# 01-CM4_Conn.net
KiCad netlist of a schematic drawn in Altium Designer
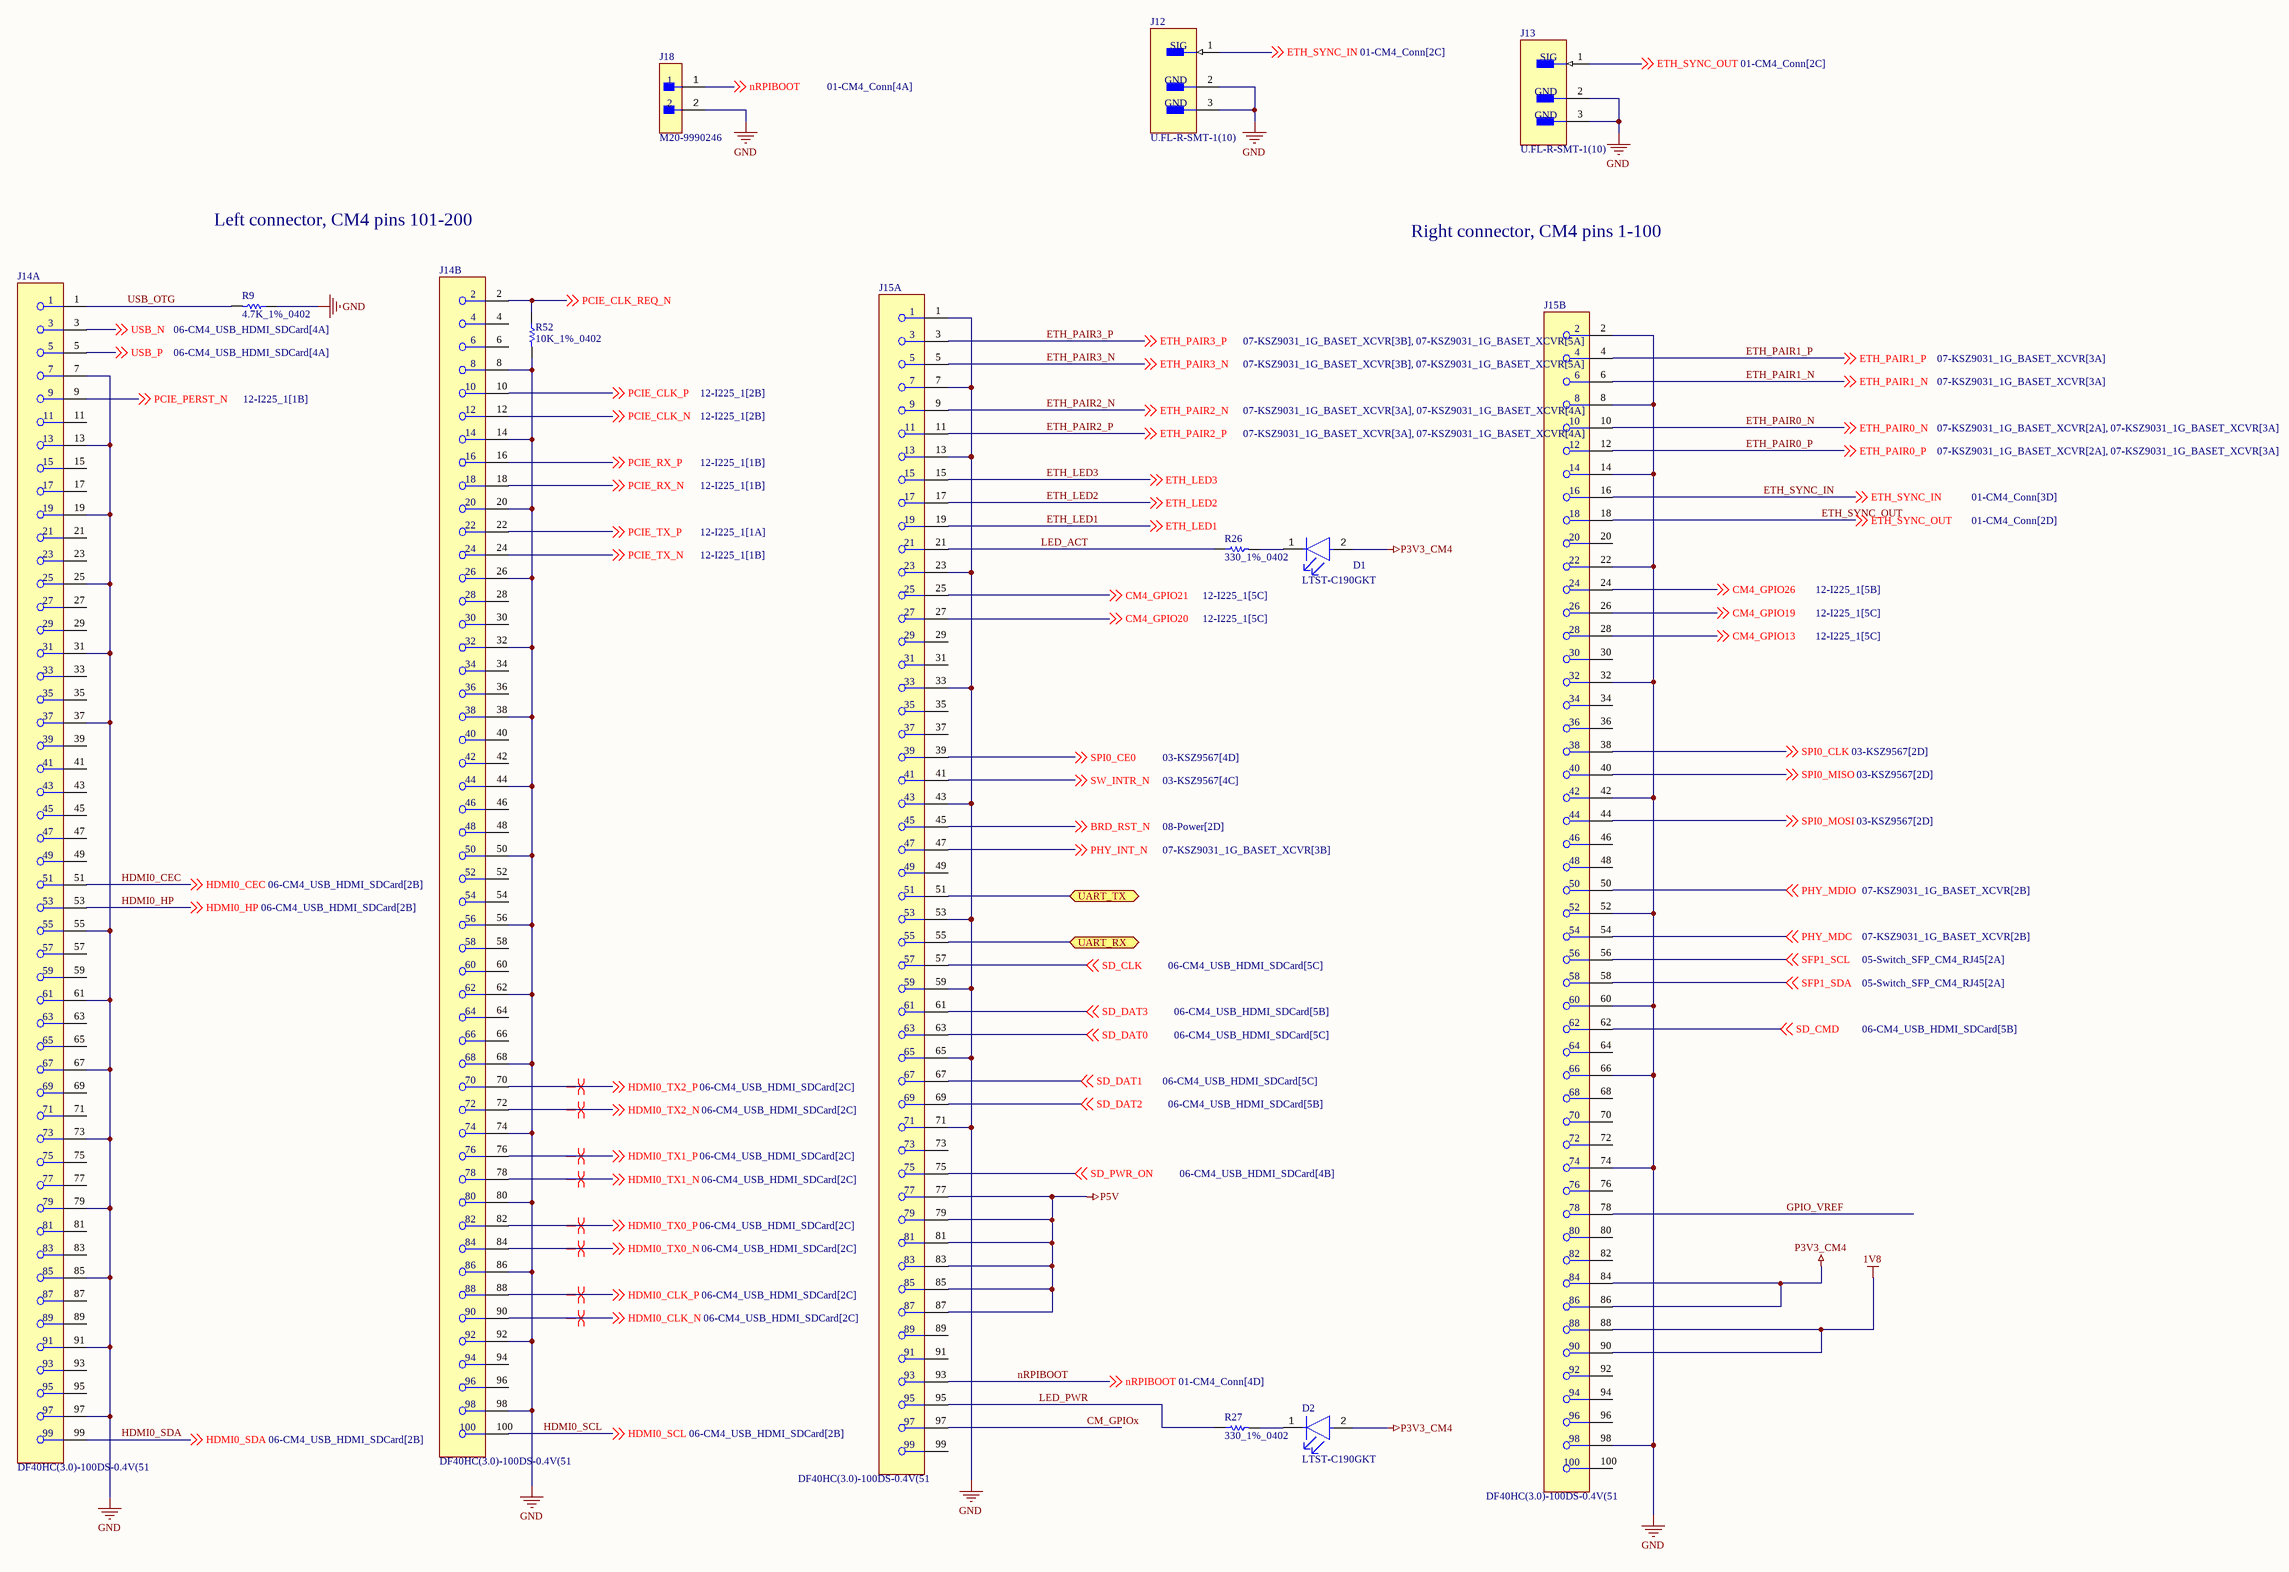
[diagram p0: 01-CM4_Conn.SchDoc]

(export (version "E")
  (design (tool "Eeschema 10.0.6"))
  (components
    (comp (ref "D1")
      (value "LTST-C190GKT")
      (footprint "FP-LTST-C190GKT-MFG")
      (description "LED GREEN CLEAR CHIP SMD")
      (fields (field (name "VOLTAGE") "2V"))
      (libsource (lib "Altium Content Vault") (part "8706943c75ba83719d021d2fdc84c58"))
    )
    (comp (ref "D2")
      (value "LTST-C190GKT")
      (footprint "FP-LTST-C190GKT-MFG")
      (description "LED GREEN CLEAR CHIP SMD")
      (fields (field (name "VOLTAGE") "2V"))
      (libsource (lib "Altium Content Vault") (part "8706943c75ba83719d021d2fdc84c58"))
    )
    (comp (ref "J12")
      (value "U.FL-R-SMT-1(10)")
      (footprint "FP-U_FL-R-SMT-1_10-MFG")
      (description "CONN U.FL RCPT STR 50 OHM SMD")
      (libsource (lib "Altium Content Vault") (part "7158abf7d987fa84906f6fb0d115710"))
    )
    (comp (ref "J13")
      (value "U.FL-R-SMT-1(10)")
      (footprint "FP-U_FL-R-SMT-1_10-MFG")
      (description "CONN U.FL RCPT STR 50 OHM SMD")
      (libsource (lib "Altium Content Vault") (part "7158abf7d987fa84906f6fb0d115710"))
    )
    (comp (ref "J14")
      (value "DF40HC(3.0)-100DS-0.4V(51")
      (footprint "FP-DF40HC_3_0_-100DS-0_4V-MFG")
      (description "CONN RCPT 100POS SMD GOLD")
      (libsource (lib "Altium Content Vault") (part "fa457dfecf3ebaea1b28843c89f182e"))
    )
    (comp (ref "J15")
      (value "DF40HC(3.0)-100DS-0.4V(51")
      (footprint "FP-DF40HC_3_0_-100DS-0_4V-MFG")
      (description "CONN RCPT 100POS SMD GOLD")
      (libsource (lib "Altium Content Vault") (part "fa457dfecf3ebaea1b28843c89f182e"))
    )
    (comp (ref "J18")
      (value "M20-9990246")
      (footprint "FP-M20-9990246-MFG")
      (description "CONN HEADER VERT 2POS 2.54MM")
      (fields
        (field (name "OCTOPART") "https://octopart.com/m20-9990246-harwin-2590635")
        (field (name "MANUFACTURER") "Harwin")
      )
      (libsource (lib "Altium Content Vault") (part "3bc925449376181038e59eaffc5286c"))
    )
    (comp (ref "R9")
      (value "4.7K_1%_0402")
      (footprint "RESC1005X40X25NL10T10")
      (fields (field (name "MANUFACTURER") "Bourns") (field (name "PART NUMBER") "CR0402-FX-4701GLF"))
      (libsource (lib "Altium Content Vault") (part "RES"))
    )
    (comp (ref "R26")
      (value "330_1%_0402")
      (footprint "RESC1005X40X25NL10T10")
      (fields (field (name "MANUFACTURER") "Panasonic") (field (name "PART NUMBER") "ERA-2AED331X"))
      (libsource (lib "Altium Content Vault") (part "RES"))
    )
    (comp (ref "R27")
      (value "330_1%_0402")
      (footprint "RESC1005X40X25NL10T10")
      (fields (field (name "MANUFACTURER") "Panasonic") (field (name "PART NUMBER") "ERA-2AED331X"))
      (libsource (lib "Altium Content Vault") (part "RES"))
    )
    (comp (ref "R52")
      (value "10K_1%_0402")
      (footprint "RESC1005X40X25NL10T10")
      (fields (field (name "MANUFACTURER") "Bourns") (field (name "PART NUMBER") "CR0402-FX-1002GLF"))
      (libsource (lib "Altium Content Vault") (part "RES"))
    )
  )
  (nets
    (net (code "1") (name "/CM_GPIOx") (class "Default")
      (node (ref "J15") (pin "97") (pinfunction "97_97") (pintype "passive"))
    )
    (net (code "2") (name "/GPIO_VREF") (class "Default")
      (node (ref "J15") (pin "78") (pinfunction "78_78") (pintype "passive"))
    )
    (net (code "3") (name "/LED_ACT") (class "Default")
      (node (ref "J15") (pin "21") (pinfunction "21_21") (pintype "passive"))
      (node (ref "R26") (pin "1") (pinfunction "1_1") (pintype "passive"))
    )
    (net (code "4") (name "/LED_PWR") (class "Default")
      (node (ref "J15") (pin "95") (pinfunction "95_95") (pintype "passive"))
      (node (ref "R27") (pin "1") (pinfunction "1_1") (pintype "passive"))
    )
    (net (code "5") (name "/UART_RX") (class "Default")
      (node (ref "J15") (pin "55") (pinfunction "55_55") (pintype "passive"))
    )
    (net (code "6") (name "/UART_TX") (class "Default")
      (node (ref "J15") (pin "51") (pinfunction "51_51") (pintype "passive"))
    )
    (net (code "7") (name "/USB_OTG") (class "Default")
      (node (ref "J14") (pin "1") (pinfunction "1_1") (pintype "passive"))
      (node (ref "R9") (pin "2") (pinfunction "2_2") (pintype "passive"))
    )
    (net (code "8") (name "1V8") (class "Default")
      (node (ref "J15") (pin "88") (pinfunction "88_88") (pintype "passive"))
      (node (ref "J15") (pin "90") (pinfunction "90_90") (pintype "passive"))
    )
    (net (code "9") (name "BRD_RST_N") (class "Default")
      (node (ref "J15") (pin "45") (pinfunction "45_45") (pintype "passive"))
    )
    (net (code "10") (name "CM4_GPIO13") (class "Default")
      (node (ref "J15") (pin "28") (pinfunction "28_28") (pintype "passive"))
    )
    (net (code "11") (name "CM4_GPIO19") (class "Default")
      (node (ref "J15") (pin "26") (pinfunction "26_26") (pintype "passive"))
    )
    (net (code "12") (name "CM4_GPIO20") (class "Default")
      (node (ref "J15") (pin "27") (pinfunction "27_27") (pintype "passive"))
    )
    (net (code "13") (name "CM4_GPIO21") (class "Default")
      (node (ref "J15") (pin "25") (pinfunction "25_25") (pintype "passive"))
    )
    (net (code "14") (name "CM4_GPIO26") (class "Default")
      (node (ref "J15") (pin "24") (pinfunction "24_24") (pintype "passive"))
    )
    (net (code "15") (name "ETH_LED1") (class "Default")
      (node (ref "J15") (pin "19") (pinfunction "19_19") (pintype "passive"))
    )
    (net (code "16") (name "ETH_LED2") (class "Default")
      (node (ref "J15") (pin "17") (pinfunction "17_17") (pintype "passive"))
    )
    (net (code "17") (name "ETH_LED3") (class "Default")
      (node (ref "J15") (pin "15") (pinfunction "15_15") (pintype "passive"))
    )
    (net (code "18") (name "ETH_PAIR0_N") (class "Default")
      (node (ref "J15") (pin "10") (pinfunction "10_10") (pintype "passive"))
    )
    (net (code "19") (name "ETH_PAIR0_P") (class "Default")
      (node (ref "J15") (pin "12") (pinfunction "12_12") (pintype "passive"))
    )
    (net (code "20") (name "ETH_PAIR1_N") (class "Default")
      (node (ref "J15") (pin "6") (pinfunction "6_6") (pintype "passive"))
    )
    (net (code "21") (name "ETH_PAIR1_P") (class "Default")
      (node (ref "J15") (pin "4") (pinfunction "4_4") (pintype "passive"))
    )
    (net (code "22") (name "ETH_PAIR2_N") (class "Default")
      (node (ref "J15") (pin "9") (pinfunction "9_9") (pintype "passive"))
    )
    (net (code "23") (name "ETH_PAIR2_P") (class "Default")
      (node (ref "J15") (pin "11") (pinfunction "11_11") (pintype "passive"))
    )
    (net (code "24") (name "ETH_PAIR3_N") (class "Default")
      (node (ref "J15") (pin "5") (pinfunction "5_5") (pintype "passive"))
    )
    (net (code "25") (name "ETH_PAIR3_P") (class "Default")
      (node (ref "J15") (pin "3") (pinfunction "3_3") (pintype "passive"))
    )
    (net (code "26") (name "ETH_SYNC_IN") (class "Default")
      (node (ref "J12") (pin "1") (pinfunction "SIG_1") (pintype "input"))
      (node (ref "J15") (pin "16") (pinfunction "16_16") (pintype "passive"))
    )
    (net (code "27") (name "ETH_SYNC_OUT") (class "Default")
      (node (ref "J13") (pin "1") (pinfunction "SIG_1") (pintype "input"))
      (node (ref "J15") (pin "18") (pinfunction "18_18") (pintype "passive"))
    )
    (net (code "28") (name "GND") (class "Default")
      (node (ref "J12") (pin "2") (pinfunction "GND_2") (pintype "power_in"))
      (node (ref "J12") (pin "3") (pinfunction "GND_3") (pintype "power_in"))
      (node (ref "J13") (pin "2") (pinfunction "GND_2") (pintype "power_in"))
      (node (ref "J13") (pin "3") (pinfunction "GND_3") (pintype "power_in"))
      (node (ref "J14") (pin "13") (pinfunction "13_13") (pintype "passive"))
      (node (ref "J14") (pin "14") (pinfunction "14_14") (pintype "passive"))
      (node (ref "J14") (pin "19") (pinfunction "19_19") (pintype "passive"))
      (node (ref "J14") (pin "20") (pinfunction "20_20") (pintype "passive"))
      (node (ref "J14") (pin "25") (pinfunction "25_25") (pintype "passive"))
      (node (ref "J14") (pin "26") (pinfunction "26_26") (pintype "passive"))
      (node (ref "J14") (pin "31") (pinfunction "31_31") (pintype "passive"))
      (node (ref "J14") (pin "32") (pinfunction "32_32") (pintype "passive"))
      (node (ref "J14") (pin "37") (pinfunction "37_37") (pintype "passive"))
      (node (ref "J14") (pin "38") (pinfunction "38_38") (pintype "passive"))
      (node (ref "J14") (pin "44") (pinfunction "44_44") (pintype "passive"))
      (node (ref "J14") (pin "50") (pinfunction "50_50") (pintype "passive"))
      (node (ref "J14") (pin "55") (pinfunction "55_55") (pintype "passive"))
      (node (ref "J14") (pin "56") (pinfunction "56_56") (pintype "passive"))
      (node (ref "J14") (pin "61") (pinfunction "61_61") (pintype "passive"))
      (node (ref "J14") (pin "62") (pinfunction "62_62") (pintype "passive"))
      (node (ref "J14") (pin "67") (pinfunction "67_67") (pintype "passive"))
      (node (ref "J14") (pin "68") (pinfunction "68_68") (pintype "passive"))
      (node (ref "J14") (pin "7") (pinfunction "7_7") (pintype "passive"))
      (node (ref "J14") (pin "73") (pinfunction "73_73") (pintype "passive"))
      (node (ref "J14") (pin "74") (pinfunction "74_74") (pintype "passive"))
      (node (ref "J14") (pin "79") (pinfunction "79_79") (pintype "passive"))
      (node (ref "J14") (pin "8") (pinfunction "8_8") (pintype "passive"))
      (node (ref "J14") (pin "80") (pinfunction "80_80") (pintype "passive"))
      (node (ref "J14") (pin "85") (pinfunction "85_85") (pintype "passive"))
      (node (ref "J14") (pin "86") (pinfunction "86_86") (pintype "passive"))
      (node (ref "J14") (pin "91") (pinfunction "91_91") (pintype "passive"))
      (node (ref "J14") (pin "92") (pinfunction "92_92") (pintype "passive"))
      (node (ref "J14") (pin "97") (pinfunction "97_97") (pintype "passive"))
      (node (ref "J14") (pin "98") (pinfunction "98_98") (pintype "passive"))
      (node (ref "J15") (pin "1") (pinfunction "1_1") (pintype "passive"))
      (node (ref "J15") (pin "13") (pinfunction "13_13") (pintype "passive"))
      (node (ref "J15") (pin "14") (pinfunction "14_14") (pintype "passive"))
      (node (ref "J15") (pin "2") (pinfunction "2_2") (pintype "passive"))
      (node (ref "J15") (pin "22") (pinfunction "22_22") (pintype "passive"))
      (node (ref "J15") (pin "23") (pinfunction "23_23") (pintype "passive"))
      (node (ref "J15") (pin "32") (pinfunction "32_32") (pintype "passive"))
      (node (ref "J15") (pin "33") (pinfunction "33_33") (pintype "passive"))
      (node (ref "J15") (pin "42") (pinfunction "42_42") (pintype "passive"))
      (node (ref "J15") (pin "43") (pinfunction "43_43") (pintype "passive"))
      (node (ref "J15") (pin "52") (pinfunction "52_52") (pintype "passive"))
      (node (ref "J15") (pin "53") (pinfunction "53_53") (pintype "passive"))
      (node (ref "J15") (pin "59") (pinfunction "59_59") (pintype "passive"))
      (node (ref "J15") (pin "60") (pinfunction "60_60") (pintype "passive"))
      (node (ref "J15") (pin "65") (pinfunction "65_65") (pintype "passive"))
      (node (ref "J15") (pin "66") (pinfunction "66_66") (pintype "passive"))
      (node (ref "J15") (pin "7") (pinfunction "7_7") (pintype "passive"))
      (node (ref "J15") (pin "71") (pinfunction "71_71") (pintype "passive"))
      (node (ref "J15") (pin "74") (pinfunction "74_74") (pintype "passive"))
      (node (ref "J15") (pin "8") (pinfunction "8_8") (pintype "passive"))
      (node (ref "J15") (pin "98") (pinfunction "98_98") (pintype "passive"))
      (node (ref "J18") (pin "2") (pinfunction "2_2") (pintype "passive"))
      (node (ref "R52") (pin "2") (pinfunction "2_2") (pintype "passive"))
      (node (ref "R9") (pin "1") (pinfunction "1_1") (pintype "passive"))
    )
    (net (code "29") (name "HDMI0_CEC") (class "Default")
      (node (ref "J14") (pin "51") (pinfunction "51_51") (pintype "passive"))
    )
    (net (code "30") (name "HDMI0_CLK_N") (class "Default")
      (node (ref "J14") (pin "90") (pinfunction "90_90") (pintype "passive"))
    )
    (net (code "31") (name "HDMI0_CLK_P") (class "Default")
      (node (ref "J14") (pin "88") (pinfunction "88_88") (pintype "passive"))
    )
    (net (code "32") (name "HDMI0_HP") (class "Default")
      (node (ref "J14") (pin "53") (pinfunction "53_53") (pintype "passive"))
    )
    (net (code "33") (name "HDMI0_SCL") (class "Default")
      (node (ref "J14") (pin "100") (pinfunction "100_100") (pintype "passive"))
    )
    (net (code "34") (name "HDMI0_SDA") (class "Default")
      (node (ref "J14") (pin "99") (pinfunction "99_99") (pintype "passive"))
    )
    (net (code "35") (name "HDMI0_TX0_N") (class "Default")
      (node (ref "J14") (pin "84") (pinfunction "84_84") (pintype "passive"))
    )
    (net (code "36") (name "HDMI0_TX0_P") (class "Default")
      (node (ref "J14") (pin "82") (pinfunction "82_82") (pintype "passive"))
    )
    (net (code "37") (name "HDMI0_TX1_N") (class "Default")
      (node (ref "J14") (pin "78") (pinfunction "78_78") (pintype "passive"))
    )
    (net (code "38") (name "HDMI0_TX1_P") (class "Default")
      (node (ref "J14") (pin "76") (pinfunction "76_76") (pintype "passive"))
    )
    (net (code "39") (name "HDMI0_TX2_N") (class "Default")
      (node (ref "J14") (pin "72") (pinfunction "72_72") (pintype "passive"))
    )
    (net (code "40") (name "HDMI0_TX2_P") (class "Default")
      (node (ref "J14") (pin "70") (pinfunction "70_70") (pintype "passive"))
    )
    (net (code "41") (name "Net-(D1-C)") (class "Default")
      (node (ref "D1") (pin "1") (pinfunction "C_1") (pintype "passive"))
      (node (ref "R26") (pin "2") (pinfunction "2_2") (pintype "passive"))
    )
    (net (code "42") (name "Net-(D2-C)") (class "Default")
      (node (ref "D2") (pin "1") (pinfunction "C_1") (pintype "passive"))
      (node (ref "R27") (pin "2") (pinfunction "2_2") (pintype "passive"))
    )
    (net (code "43") (name "P3V3_CM4") (class "Default")
      (node (ref "D1") (pin "2") (pinfunction "A_2") (pintype "passive"))
      (node (ref "D2") (pin "2") (pinfunction "A_2") (pintype "passive"))
      (node (ref "J15") (pin "84") (pinfunction "84_84") (pintype "passive"))
      (node (ref "J15") (pin "86") (pinfunction "86_86") (pintype "passive"))
    )
    (net (code "44") (name "P5V") (class "Default")
      (node (ref "J15") (pin "77") (pinfunction "77_77") (pintype "passive"))
      (node (ref "J15") (pin "79") (pinfunction "79_79") (pintype "passive"))
      (node (ref "J15") (pin "81") (pinfunction "81_81") (pintype "passive"))
      (node (ref "J15") (pin "83") (pinfunction "83_83") (pintype "passive"))
      (node (ref "J15") (pin "85") (pinfunction "85_85") (pintype "passive"))
      (node (ref "J15") (pin "87") (pinfunction "87_87") (pintype "passive"))
    )
    (net (code "45") (name "PCIE_CLK_N") (class "Default")
      (node (ref "J14") (pin "12") (pinfunction "12_12") (pintype "passive"))
    )
    (net (code "46") (name "PCIE_CLK_P") (class "Default")
      (node (ref "J14") (pin "10") (pinfunction "10_10") (pintype "passive"))
    )
    (net (code "47") (name "PCIE_CLK_REQ_N") (class "Default")
      (node (ref "J14") (pin "2") (pinfunction "2_2") (pintype "passive"))
      (node (ref "R52") (pin "1") (pinfunction "1_1") (pintype "passive"))
    )
    (net (code "48") (name "PCIE_PERST_N") (class "Default")
      (node (ref "J14") (pin "9") (pinfunction "9_9") (pintype "passive"))
    )
    (net (code "49") (name "PCIE_RX_N") (class "Default")
      (node (ref "J14") (pin "18") (pinfunction "18_18") (pintype "passive"))
    )
    (net (code "50") (name "PCIE_RX_P") (class "Default")
      (node (ref "J14") (pin "16") (pinfunction "16_16") (pintype "passive"))
    )
    (net (code "51") (name "PCIE_TX_N") (class "Default")
      (node (ref "J14") (pin "24") (pinfunction "24_24") (pintype "passive"))
    )
    (net (code "52") (name "PCIE_TX_P") (class "Default")
      (node (ref "J14") (pin "22") (pinfunction "22_22") (pintype "passive"))
    )
    (net (code "53") (name "PHY_INT_N") (class "Default")
      (node (ref "J15") (pin "47") (pinfunction "47_47") (pintype "passive"))
    )
    (net (code "54") (name "PHY_MDC") (class "Default")
      (node (ref "J15") (pin "54") (pinfunction "54_54") (pintype "passive"))
    )
    (net (code "55") (name "PHY_MDIO") (class "Default")
      (node (ref "J15") (pin "50") (pinfunction "50_50") (pintype "passive"))
    )
    (net (code "56") (name "SD_CLK") (class "Default")
      (node (ref "J15") (pin "57") (pinfunction "57_57") (pintype "passive"))
    )
    (net (code "57") (name "SD_CMD") (class "Default")
      (node (ref "J15") (pin "62") (pinfunction "62_62") (pintype "passive"))
    )
    (net (code "58") (name "SD_DAT0") (class "Default")
      (node (ref "J15") (pin "63") (pinfunction "63_63") (pintype "passive"))
    )
    (net (code "59") (name "SD_DAT1") (class "Default")
      (node (ref "J15") (pin "67") (pinfunction "67_67") (pintype "passive"))
    )
    (net (code "60") (name "SD_DAT2") (class "Default")
      (node (ref "J15") (pin "69") (pinfunction "69_69") (pintype "passive"))
    )
    (net (code "61") (name "SD_DAT3") (class "Default")
      (node (ref "J15") (pin "61") (pinfunction "61_61") (pintype "passive"))
    )
    (net (code "62") (name "SD_PWR_ON") (class "Default")
      (node (ref "J15") (pin "75") (pinfunction "75_75") (pintype "passive"))
    )
    (net (code "63") (name "SFP1_SCL") (class "Default")
      (node (ref "J15") (pin "56") (pinfunction "56_56") (pintype "passive"))
    )
    (net (code "64") (name "SFP1_SDA") (class "Default")
      (node (ref "J15") (pin "58") (pinfunction "58_58") (pintype "passive"))
    )
    (net (code "65") (name "SPI0_CE0") (class "Default")
      (node (ref "J15") (pin "39") (pinfunction "39_39") (pintype "passive"))
    )
    (net (code "66") (name "SPI0_CLK") (class "Default")
      (node (ref "J15") (pin "38") (pinfunction "38_38") (pintype "passive"))
    )
    (net (code "67") (name "SPI0_MISO") (class "Default")
      (node (ref "J15") (pin "40") (pinfunction "40_40") (pintype "passive"))
    )
    (net (code "68") (name "SPI0_MOSI") (class "Default")
      (node (ref "J15") (pin "44") (pinfunction "44_44") (pintype "passive"))
    )
    (net (code "69") (name "SW_INTR_N") (class "Default")
      (node (ref "J15") (pin "41") (pinfunction "41_41") (pintype "passive"))
    )
    (net (code "70") (name "USB_N") (class "Default")
      (node (ref "J14") (pin "3") (pinfunction "3_3") (pintype "passive"))
    )
    (net (code "71") (name "USB_P") (class "Default")
      (node (ref "J14") (pin "5") (pinfunction "5_5") (pintype "passive"))
    )
    (net (code "72") (name "nRPIBOOT") (class "Default")
      (node (ref "J15") (pin "93") (pinfunction "93_93") (pintype "passive"))
      (node (ref "J18") (pin "1") (pinfunction "1_1") (pintype "passive"))
    )
    (net (code "73") (name "unconnected-(J14-Pad4)") (class "Default")
      (node (ref "J14") (pin "4") (pinfunction "4_4") (pintype "passive"))
    )
    (net (code "74") (name "unconnected-(J14-Pad6)") (class "Default")
      (node (ref "J14") (pin "6") (pinfunction "6_6") (pintype "passive"))
    )
    (net (code "75") (name "unconnected-(J14-Pad11)") (class "Default")
      (node (ref "J14") (pin "11") (pinfunction "11_11") (pintype "passive"))
    )
    (net (code "76") (name "unconnected-(J14-Pad15)") (class "Default")
      (node (ref "J14") (pin "15") (pinfunction "15_15") (pintype "passive"))
    )
    (net (code "77") (name "unconnected-(J14-Pad17)") (class "Default")
      (node (ref "J14") (pin "17") (pinfunction "17_17") (pintype "passive"))
    )
    (net (code "78") (name "unconnected-(J14-Pad21)") (class "Default")
      (node (ref "J14") (pin "21") (pinfunction "21_21") (pintype "passive"))
    )
    (net (code "79") (name "unconnected-(J14-Pad23)") (class "Default")
      (node (ref "J14") (pin "23") (pinfunction "23_23") (pintype "passive"))
    )
    (net (code "80") (name "unconnected-(J14-Pad27)") (class "Default")
      (node (ref "J14") (pin "27") (pinfunction "27_27") (pintype "passive"))
    )
    (net (code "81") (name "unconnected-(J14-Pad28)") (class "Default")
      (node (ref "J14") (pin "28") (pinfunction "28_28") (pintype "passive"))
    )
    (net (code "82") (name "unconnected-(J14-Pad29)") (class "Default")
      (node (ref "J14") (pin "29") (pinfunction "29_29") (pintype "passive"))
    )
    (net (code "83") (name "unconnected-(J14-Pad30)") (class "Default")
      (node (ref "J14") (pin "30") (pinfunction "30_30") (pintype "passive"))
    )
    (net (code "84") (name "unconnected-(J14-Pad33)") (class "Default")
      (node (ref "J14") (pin "33") (pinfunction "33_33") (pintype "passive"))
    )
    (net (code "85") (name "unconnected-(J14-Pad34)") (class "Default")
      (node (ref "J14") (pin "34") (pinfunction "34_34") (pintype "passive"))
    )
    (net (code "86") (name "unconnected-(J14-Pad35)") (class "Default")
      (node (ref "J14") (pin "35") (pinfunction "35_35") (pintype "passive"))
    )
    (net (code "87") (name "unconnected-(J14-Pad36)") (class "Default")
      (node (ref "J14") (pin "36") (pinfunction "36_36") (pintype "passive"))
    )
    (net (code "88") (name "unconnected-(J14-Pad39)") (class "Default")
      (node (ref "J14") (pin "39") (pinfunction "39_39") (pintype "passive"))
    )
    (net (code "89") (name "unconnected-(J14-Pad40)") (class "Default")
      (node (ref "J14") (pin "40") (pinfunction "40_40") (pintype "passive"))
    )
    (net (code "90") (name "unconnected-(J14-Pad41)") (class "Default")
      (node (ref "J14") (pin "41") (pinfunction "41_41") (pintype "passive"))
    )
    (net (code "91") (name "unconnected-(J14-Pad42)") (class "Default")
      (node (ref "J14") (pin "42") (pinfunction "42_42") (pintype "passive"))
    )
    (net (code "92") (name "unconnected-(J14-Pad43)") (class "Default")
      (node (ref "J14") (pin "43") (pinfunction "43_43") (pintype "passive"))
    )
    (net (code "93") (name "unconnected-(J14-Pad45)") (class "Default")
      (node (ref "J14") (pin "45") (pinfunction "45_45") (pintype "passive"))
    )
    (net (code "94") (name "unconnected-(J14-Pad46)") (class "Default")
      (node (ref "J14") (pin "46") (pinfunction "46_46") (pintype "passive"))
    )
    (net (code "95") (name "unconnected-(J14-Pad47)") (class "Default")
      (node (ref "J14") (pin "47") (pinfunction "47_47") (pintype "passive"))
    )
    (net (code "96") (name "unconnected-(J14-Pad48)") (class "Default")
      (node (ref "J14") (pin "48") (pinfunction "48_48") (pintype "passive"))
    )
    (net (code "97") (name "unconnected-(J14-Pad49)") (class "Default")
      (node (ref "J14") (pin "49") (pinfunction "49_49") (pintype "passive"))
    )
    (net (code "98") (name "unconnected-(J14-Pad52)") (class "Default")
      (node (ref "J14") (pin "52") (pinfunction "52_52") (pintype "passive"))
    )
    (net (code "99") (name "unconnected-(J14-Pad54)") (class "Default")
      (node (ref "J14") (pin "54") (pinfunction "54_54") (pintype "passive"))
    )
    (net (code "100") (name "unconnected-(J14-Pad57)") (class "Default")
      (node (ref "J14") (pin "57") (pinfunction "57_57") (pintype "passive"))
    )
    (net (code "101") (name "unconnected-(J14-Pad58)") (class "Default")
      (node (ref "J14") (pin "58") (pinfunction "58_58") (pintype "passive"))
    )
    (net (code "102") (name "unconnected-(J14-Pad59)") (class "Default")
      (node (ref "J14") (pin "59") (pinfunction "59_59") (pintype "passive"))
    )
    (net (code "103") (name "unconnected-(J14-Pad60)") (class "Default")
      (node (ref "J14") (pin "60") (pinfunction "60_60") (pintype "passive"))
    )
    (net (code "104") (name "unconnected-(J14-Pad63)") (class "Default")
      (node (ref "J14") (pin "63") (pinfunction "63_63") (pintype "passive"))
    )
    (net (code "105") (name "unconnected-(J14-Pad64)") (class "Default")
      (node (ref "J14") (pin "64") (pinfunction "64_64") (pintype "passive"))
    )
    (net (code "106") (name "unconnected-(J14-Pad65)") (class "Default")
      (node (ref "J14") (pin "65") (pinfunction "65_65") (pintype "passive"))
    )
    (net (code "107") (name "unconnected-(J14-Pad66)") (class "Default")
      (node (ref "J14") (pin "66") (pinfunction "66_66") (pintype "passive"))
    )
    (net (code "108") (name "unconnected-(J14-Pad69)") (class "Default")
      (node (ref "J14") (pin "69") (pinfunction "69_69") (pintype "passive"))
    )
    (net (code "109") (name "unconnected-(J14-Pad71)") (class "Default")
      (node (ref "J14") (pin "71") (pinfunction "71_71") (pintype "passive"))
    )
    (net (code "110") (name "unconnected-(J14-Pad75)") (class "Default")
      (node (ref "J14") (pin "75") (pinfunction "75_75") (pintype "passive"))
    )
    (net (code "111") (name "unconnected-(J14-Pad77)") (class "Default")
      (node (ref "J14") (pin "77") (pinfunction "77_77") (pintype "passive"))
    )
    (net (code "112") (name "unconnected-(J14-Pad81)") (class "Default")
      (node (ref "J14") (pin "81") (pinfunction "81_81") (pintype "passive"))
    )
    (net (code "113") (name "unconnected-(J14-Pad83)") (class "Default")
      (node (ref "J14") (pin "83") (pinfunction "83_83") (pintype "passive"))
    )
    (net (code "114") (name "unconnected-(J14-Pad87)") (class "Default")
      (node (ref "J14") (pin "87") (pinfunction "87_87") (pintype "passive"))
    )
    (net (code "115") (name "unconnected-(J14-Pad89)") (class "Default")
      (node (ref "J14") (pin "89") (pinfunction "89_89") (pintype "passive"))
    )
    (net (code "116") (name "unconnected-(J14-Pad93)") (class "Default")
      (node (ref "J14") (pin "93") (pinfunction "93_93") (pintype "passive"))
    )
    (net (code "117") (name "unconnected-(J14-Pad94)") (class "Default")
      (node (ref "J14") (pin "94") (pinfunction "94_94") (pintype "passive"))
    )
    (net (code "118") (name "unconnected-(J14-Pad95)") (class "Default")
      (node (ref "J14") (pin "95") (pinfunction "95_95") (pintype "passive"))
    )
    (net (code "119") (name "unconnected-(J14-Pad96)") (class "Default")
      (node (ref "J14") (pin "96") (pinfunction "96_96") (pintype "passive"))
    )
    (net (code "120") (name "unconnected-(J15-Pad20)") (class "Default")
      (node (ref "J15") (pin "20") (pinfunction "20_20") (pintype "passive"))
    )
    (net (code "121") (name "unconnected-(J15-Pad29)") (class "Default")
      (node (ref "J15") (pin "29") (pinfunction "29_29") (pintype "passive"))
    )
    (net (code "122") (name "unconnected-(J15-Pad30)") (class "Default")
      (node (ref "J15") (pin "30") (pinfunction "30_30") (pintype "passive"))
    )
    (net (code "123") (name "unconnected-(J15-Pad31)") (class "Default")
      (node (ref "J15") (pin "31") (pinfunction "31_31") (pintype "passive"))
    )
    (net (code "124") (name "unconnected-(J15-Pad34)") (class "Default")
      (node (ref "J15") (pin "34") (pinfunction "34_34") (pintype "passive"))
    )
    (net (code "125") (name "unconnected-(J15-Pad35)") (class "Default")
      (node (ref "J15") (pin "35") (pinfunction "35_35") (pintype "passive"))
    )
    (net (code "126") (name "unconnected-(J15-Pad36)") (class "Default")
      (node (ref "J15") (pin "36") (pinfunction "36_36") (pintype "passive"))
    )
    (net (code "127") (name "unconnected-(J15-Pad37)") (class "Default")
      (node (ref "J15") (pin "37") (pinfunction "37_37") (pintype "passive"))
    )
    (net (code "128") (name "unconnected-(J15-Pad46)") (class "Default")
      (node (ref "J15") (pin "46") (pinfunction "46_46") (pintype "passive"))
    )
    (net (code "129") (name "unconnected-(J15-Pad48)") (class "Default")
      (node (ref "J15") (pin "48") (pinfunction "48_48") (pintype "passive"))
    )
    (net (code "130") (name "unconnected-(J15-Pad49)") (class "Default")
      (node (ref "J15") (pin "49") (pinfunction "49_49") (pintype "passive"))
    )
    (net (code "131") (name "unconnected-(J15-Pad64)") (class "Default")
      (node (ref "J15") (pin "64") (pinfunction "64_64") (pintype "passive"))
    )
    (net (code "132") (name "unconnected-(J15-Pad68)") (class "Default")
      (node (ref "J15") (pin "68") (pinfunction "68_68") (pintype "passive"))
    )
    (net (code "133") (name "unconnected-(J15-Pad70)") (class "Default")
      (node (ref "J15") (pin "70") (pinfunction "70_70") (pintype "passive"))
    )
    (net (code "134") (name "unconnected-(J15-Pad72)") (class "Default")
      (node (ref "J15") (pin "72") (pinfunction "72_72") (pintype "passive"))
    )
    (net (code "135") (name "unconnected-(J15-Pad73)") (class "Default")
      (node (ref "J15") (pin "73") (pinfunction "73_73") (pintype "passive"))
    )
    (net (code "136") (name "unconnected-(J15-Pad76)") (class "Default")
      (node (ref "J15") (pin "76") (pinfunction "76_76") (pintype "passive"))
    )
    (net (code "137") (name "unconnected-(J15-Pad80)") (class "Default")
      (node (ref "J15") (pin "80") (pinfunction "80_80") (pintype "passive"))
    )
    (net (code "138") (name "unconnected-(J15-Pad82)") (class "Default")
      (node (ref "J15") (pin "82") (pinfunction "82_82") (pintype "passive"))
    )
    (net (code "139") (name "unconnected-(J15-Pad89)") (class "Default")
      (node (ref "J15") (pin "89") (pinfunction "89_89") (pintype "passive"))
    )
    (net (code "140") (name "unconnected-(J15-Pad91)") (class "Default")
      (node (ref "J15") (pin "91") (pinfunction "91_91") (pintype "passive"))
    )
    (net (code "141") (name "unconnected-(J15-Pad92)") (class "Default")
      (node (ref "J15") (pin "92") (pinfunction "92_92") (pintype "passive"))
    )
    (net (code "142") (name "unconnected-(J15-Pad94)") (class "Default")
      (node (ref "J15") (pin "94") (pinfunction "94_94") (pintype "passive"))
    )
    (net (code "143") (name "unconnected-(J15-Pad96)") (class "Default")
      (node (ref "J15") (pin "96") (pinfunction "96_96") (pintype "passive"))
    )
    (net (code "144") (name "unconnected-(J15-Pad99)") (class "Default")
      (node (ref "J15") (pin "99") (pinfunction "99_99") (pintype "passive"))
    )
    (net (code "145") (name "unconnected-(J15-Pad100)") (class "Default")
      (node (ref "J15") (pin "100") (pinfunction "100_100") (pintype "passive"))
    )
  )
)
